# MURI_Compass_V3.net
KiCad netlist of a schematic drawn in EAGLE
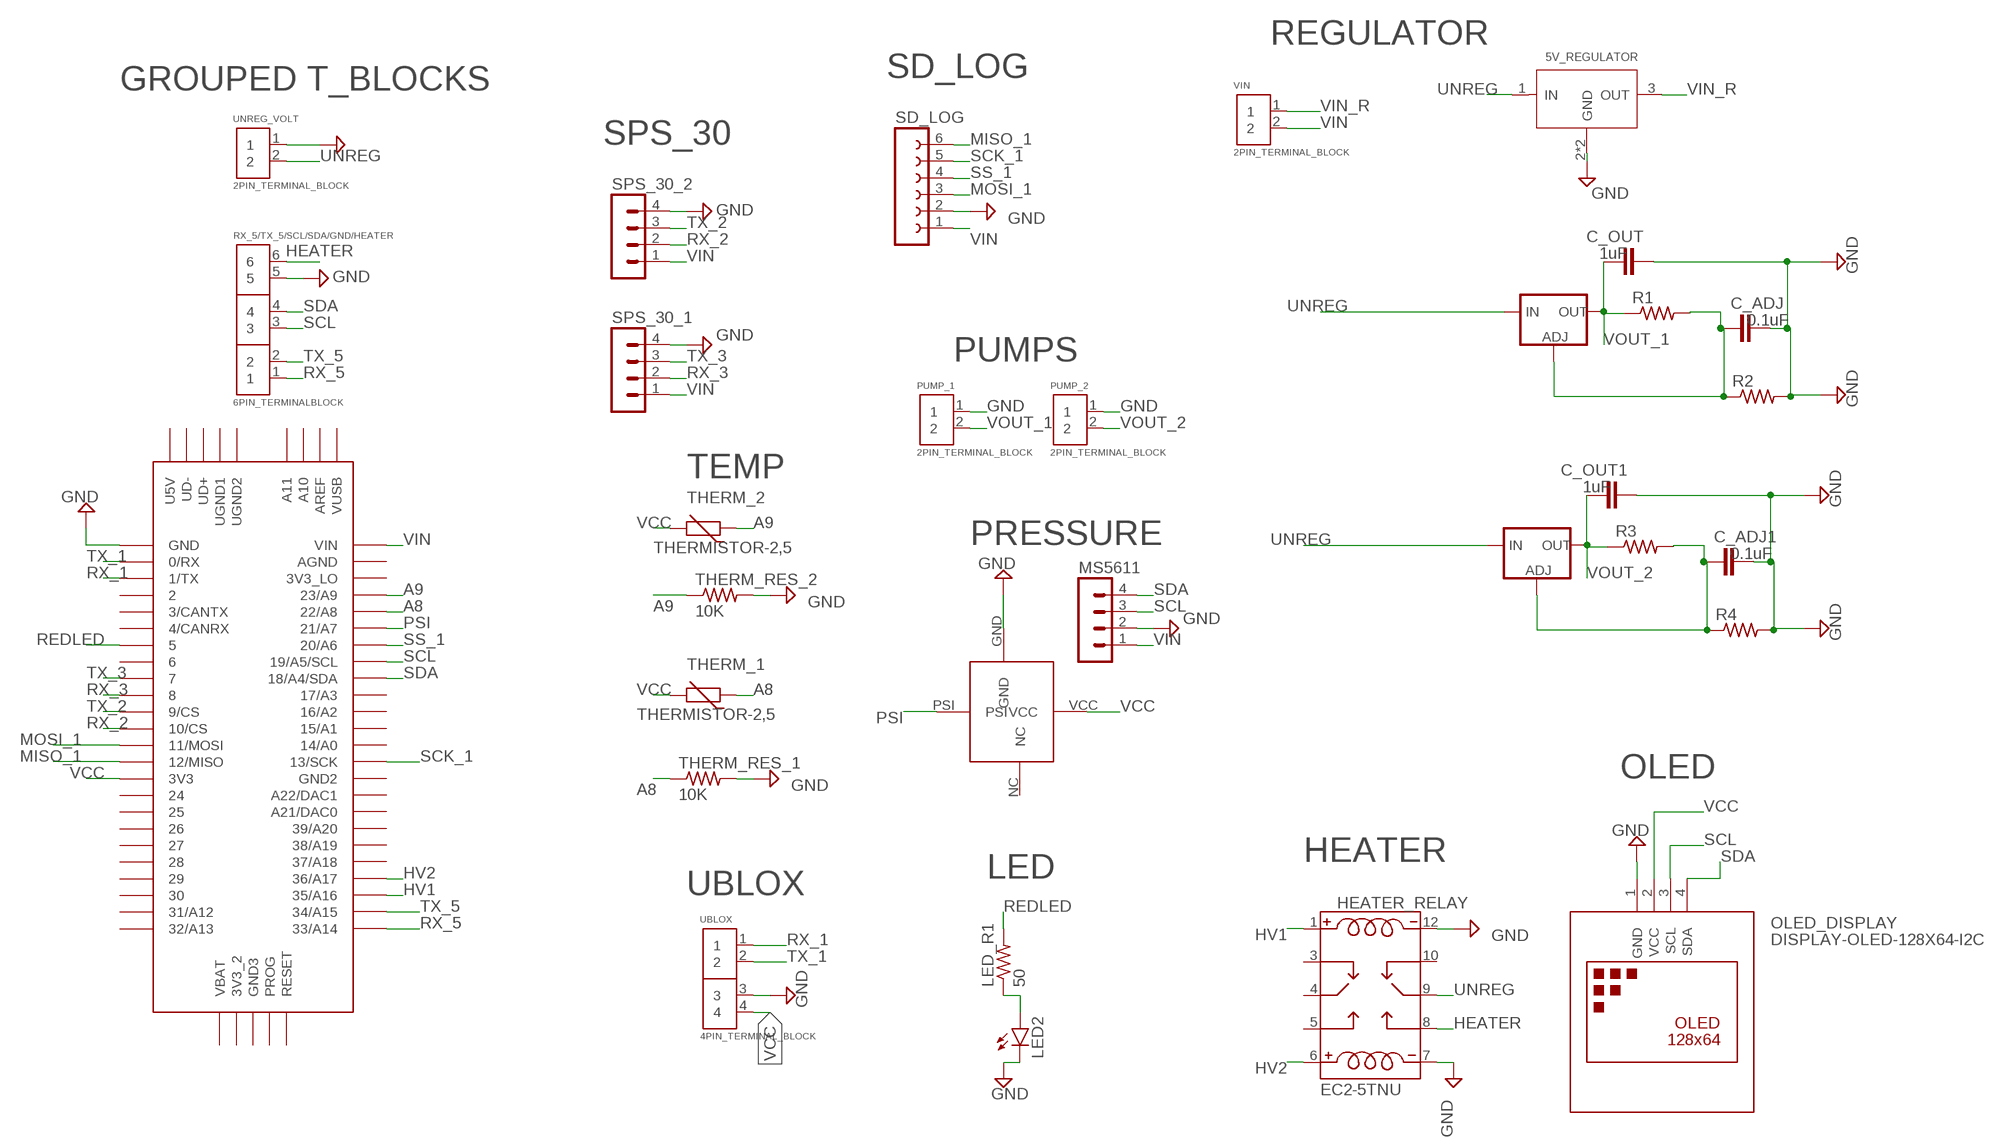
[diagram p0: schematic, sheet 1]

(export (version "E")
  (design (tool "Eeschema 10.0.6"))
  (components
    (comp (ref "5V_REGULATOR")
      (value "PMIC-L7805CV-DG(TO-220)")
      (footprint "eagle-import:TO-220")
      (fields
        (field (name "DIGI-KEY_PART_NUMBER") "497-12404-ND")
        (field (name "MF") "STMicroelectronics")
        (field (name "MP") "L7805CV-DG")
      )
      (libsource (lib "eagle-import") (part "PMIC-L7805CV-DG(TO-220)"))
    )
    (comp (ref "C_ADJ")
      (value "0.1uF")
      (footprint "eagle-import:C2.5-3")
      (libsource (lib "eagle-import") (part "C2,5-3"))
    )
    (comp (ref "C_ADJ1")
      (value "0.1uF")
      (footprint "eagle-import:C2.5-3")
      (libsource (lib "eagle-import") (part "C2,5-3"))
    )
    (comp (ref "C_OUT")
      (value "1uF")
      (footprint "eagle-import:C2.5-3")
      (libsource (lib "eagle-import") (part "C2,5-3"))
    )
    (comp (ref "C_OUT1")
      (value "1uF")
      (footprint "eagle-import:C2.5-3")
      (libsource (lib "eagle-import") (part "C2,5-3"))
    )
    (comp (ref "HEATER_RELAY")
      (value "EC2-5TNU")
      (footprint "eagle-import:RELAY_EC2-5TNU")
      (fields (field (name "MF") "KEMET"))
      (libsource (lib "eagle-import") (part "EC2-5TNU"))
    )
    (comp (ref "LED2")
      (value "TLLR4400")
      (footprint "eagle-import:LED3MM")
      (fields (field (name "MF") "VISHAY SEMICONDUCTOR"))
      (libsource (lib "eagle-import") (part "TLLR4400"))
    )
    (comp (ref "LED_R1")
      (value "50")
      (footprint "eagle-import:0204_7")
      (libsource (lib "eagle-import") (part "resistor_348_R-US_0204/7"))
    )
    (comp (ref "MS5611")
      (value "MA04-1")
      (footprint "eagle-import:MA04-1")
      (libsource (lib "eagle-import") (part "MA04-1"))
    )
    (comp (ref "OLED_DISPLAY")
      (value "DISPLAY-OLED-128X64-I2C")
      (footprint "eagle-import:DISPLAY-OLED-128X64-I2C")
      (libsource (lib "eagle-import") (part "DISPLAY-OLED-128X64-I2C"))
    )
    (comp (ref "PRESSURE_SENSOR")
      (value "SSCSANN015PAAA5")
      (footprint "eagle-import:SSCSANN015PAAA5")
      (libsource (lib "eagle-import") (part "SSCSANN015PAAA5"))
    )
    (comp (ref "PUMP_1")
      (value "2PIN_TERMINAL_BLOCK")
      (footprint "eagle-import:2PIN_TERMINAL_BLOCK")
      (fields
        (field (name "COMMENT") "282834-2")
        (field (name "DIGI-KEY_PART_NUMBER") "A98333-ND")
        (field (name "MF") "TE Connectivity")
      )
      (libsource (lib "eagle-import") (part "2PIN_TERMINAL_BLOCK"))
    )
    (comp (ref "PUMP_2")
      (value "2PIN_TERMINAL_BLOCK")
      (footprint "eagle-import:2PIN_TERMINAL_BLOCK")
      (fields
        (field (name "COMMENT") "282834-2")
        (field (name "DIGI-KEY_PART_NUMBER") "A98333-ND")
        (field (name "MF") "TE Connectivity")
      )
      (libsource (lib "eagle-import") (part "2PIN_TERMINAL_BLOCK"))
    )
    (comp (ref "R1")
      (value "R-US_0204/7")
      (footprint "eagle-import:0204_7")
      (libsource (lib "eagle-import") (part "R-US_0204/7"))
    )
    (comp (ref "R2")
      (value "R-US_0204/7")
      (footprint "eagle-import:0204_7")
      (libsource (lib "eagle-import") (part "R-US_0204/7"))
    )
    (comp (ref "R3")
      (value "R-US_0204/7")
      (footprint "eagle-import:0204_7")
      (libsource (lib "eagle-import") (part "R-US_0204/7"))
    )
    (comp (ref "R4")
      (value "R-US_0204/7")
      (footprint "eagle-import:0204_7")
      (libsource (lib "eagle-import") (part "R-US_0204/7"))
    )
    (comp (ref "RX_5/TX_5/SCL/SDA/GND/HEATER")
      (value "6PIN_TERMINALBLOCK")
      (footprint "eagle-import:6PIN_TERMINALBLOCK")
      (libsource (lib "eagle-import") (part "6PIN_TERMINALBLOCK"))
    )
    (comp (ref "SD_LOG")
      (value "FE06-1")
      (footprint "eagle-import:FE06")
      (libsource (lib "eagle-import") (part "FE06-1"))
    )
    (comp (ref "SPS_30_1")
      (value "MA04-1")
      (footprint "eagle-import:MA04-1")
      (libsource (lib "eagle-import") (part "MA04-1"))
    )
    (comp (ref "SPS_30_2")
      (value "MA04-1")
      (footprint "eagle-import:MA04-1")
      (libsource (lib "eagle-import") (part "MA04-1"))
    )
    (comp (ref "THERM_1")
      (value "THERMISTOR-2,5")
      (footprint "eagle-import:RS-2,5")
      (libsource (lib "eagle-import") (part "THERMISTOR-2,5"))
    )
    (comp (ref "THERM_2")
      (value "THERMISTOR-2,5")
      (footprint "eagle-import:RS-2,5")
      (libsource (lib "eagle-import") (part "THERMISTOR-2,5"))
    )
    (comp (ref "THERM_RES_1")
      (value "10K")
      (footprint "eagle-import:0204_7")
      (libsource (lib "eagle-import") (part "R-US_0204/7"))
    )
    (comp (ref "THERM_RES_2")
      (value "10K")
      (footprint "eagle-import:0204_7")
      (libsource (lib "eagle-import") (part "R-US_0204/7"))
    )
    (comp (ref "U$1")
      (value "TEENSY_3.5/3.6")
      (footprint "eagle-import:TEENSY_3.5_3.6")
      (libsource (lib "eagle-import") (part "TEENSY_3.5/3.6"))
    )
    (comp (ref "U1")
      (value "V_REG_317SINK")
      (footprint "eagle-import:TO220-ADJ")
      (libsource (lib "eagle-import") (part "V_REG_317SINK"))
    )
    (comp (ref "U2")
      (value "V_REG_317SINK")
      (footprint "eagle-import:TO220-ADJ")
      (libsource (lib "eagle-import") (part "V_REG_317SINK"))
    )
    (comp (ref "UBLOX")
      (value "4PIN_TERMINAL_BLOCK")
      (footprint "eagle-import:4PIN_TERMINAL_BLOCK")
      (libsource (lib "eagle-import") (part "4PIN_TERMINAL_BLOCK"))
    )
    (comp (ref "UNREG_VOLT")
      (value "2PIN_TERMINAL_BLOCK")
      (footprint "eagle-import:2PIN_TERMINAL_BLOCK")
      (fields
        (field (name "COMMENT") "282834-2")
        (field (name "DIGI-KEY_PART_NUMBER") "A98333-ND")
        (field (name "MF") "TE Connectivity")
      )
      (libsource (lib "eagle-import") (part "2PIN_TERMINAL_BLOCK"))
    )
    (comp (ref "VIN")
      (value "2PIN_TERMINAL_BLOCK")
      (footprint "eagle-import:2PIN_TERMINAL_BLOCK")
      (fields
        (field (name "COMMENT") "282834-2")
        (field (name "DIGI-KEY_PART_NUMBER") "A98333-ND")
        (field (name "MF") "TE Connectivity")
      )
      (libsource (lib "eagle-import") (part "2PIN_TERMINAL_BLOCK"))
    )
  )
  (nets
    (net (code "1") (name "/A8") (class "Default")
      (node (ref "THERM_1") (pin "1") (pinfunction "1_1") (pintype "passive"))
      (node (ref "THERM_RES_1") (pin "1") (pinfunction "1_1") (pintype "passive"))
      (node (ref "U$1") (pin "22/A8") (pinfunction "22/A8_22/A8") (pintype "bidirectional"))
    )
    (net (code "2") (name "/A9") (class "Default")
      (node (ref "THERM_2") (pin "1") (pinfunction "1_1") (pintype "passive"))
      (node (ref "THERM_RES_2") (pin "1") (pinfunction "1_1") (pintype "passive"))
      (node (ref "U$1") (pin "23/A9") (pinfunction "23/A9_23/A9") (pintype "bidirectional"))
    )
    (net (code "3") (name "/HEATER") (class "Default")
      (node (ref "HEATER_RELAY") (pin "8") (pinfunction "NO_8") (pintype "passive"))
      (node (ref "RX_5/TX_5/SCL/SDA/GND/HEATER") (pin "6") (pinfunction "6_6") (pintype "passive"))
    )
    (net (code "4") (name "/HV1") (class "Default")
      (node (ref "HEATER_RELAY") (pin "1") (pinfunction "C1_1") (pintype "passive"))
      (node (ref "U$1") (pin "35/A16") (pinfunction "35/A16_35/A16") (pintype "bidirectional"))
    )
    (net (code "5") (name "/HV2") (class "Default")
      (node (ref "HEATER_RELAY") (pin "6") (pinfunction "C3_6") (pintype "passive"))
      (node (ref "U$1") (pin "36/A17") (pinfunction "36/A17_36/A17") (pintype "bidirectional"))
    )
    (net (code "6") (name "/MISO_1") (class "Default")
      (node (ref "SD_LOG") (pin "6") (pinfunction "6_6") (pintype "passive"))
      (node (ref "U$1") (pin "12/MISO") (pinfunction "12/MISO_12/MISO") (pintype "bidirectional"))
    )
    (net (code "7") (name "/MOSI_1") (class "Default")
      (node (ref "SD_LOG") (pin "3") (pinfunction "3_3") (pintype "passive"))
      (node (ref "U$1") (pin "11/MOSI") (pinfunction "11/MOSI_11/MOSI") (pintype "bidirectional"))
    )
    (net (code "8") (name "/PSI") (class "Default")
      (node (ref "PRESSURE_SENSOR") (pin "PSI") (pinfunction "PSI_PSI") (pintype "bidirectional"))
      (node (ref "U$1") (pin "21/A7") (pinfunction "21/A7_21/A7") (pintype "bidirectional"))
    )
    (net (code "9") (name "/REDLED") (class "Default")
      (node (ref "LED_R1") (pin "2") (pinfunction "2_2") (pintype "passive"))
      (node (ref "U$1") (pin "5") (pinfunction "5_5") (pintype "bidirectional"))
    )
    (net (code "10") (name "/RX_1") (class "Default")
      (node (ref "U$1") (pin "1/TX") (pinfunction "1/TX_1/TX") (pintype "bidirectional"))
      (node (ref "UBLOX") (pin "1") (pinfunction "1_1") (pintype "passive"))
    )
    (net (code "11") (name "/RX_2") (class "Default")
      (node (ref "SPS_30_2") (pin "2") (pinfunction "2_2") (pintype "passive"))
      (node (ref "U$1") (pin "10/CS") (pinfunction "10/CS_10/CS") (pintype "bidirectional"))
    )
    (net (code "12") (name "/RX_3") (class "Default")
      (node (ref "SPS_30_1") (pin "2") (pinfunction "2_2") (pintype "passive"))
      (node (ref "U$1") (pin "8") (pinfunction "8_8") (pintype "bidirectional"))
    )
    (net (code "13") (name "/RX_5") (class "Default")
      (node (ref "RX_5/TX_5/SCL/SDA/GND/HEATER") (pin "1") (pinfunction "1_1") (pintype "passive"))
      (node (ref "U$1") (pin "33/A14") (pinfunction "33/A14_33/A14") (pintype "bidirectional"))
    )
    (net (code "14") (name "/SCK_1") (class "Default")
      (node (ref "SD_LOG") (pin "5") (pinfunction "5_5") (pintype "passive"))
      (node (ref "U$1") (pin "13/SCK") (pinfunction "13/SCK_13/SCK") (pintype "bidirectional"))
    )
    (net (code "15") (name "/SCL") (class "Default")
      (node (ref "MS5611") (pin "3") (pinfunction "3_3") (pintype "passive"))
      (node (ref "OLED_DISPLAY") (pin "3") (pinfunction "SCL_3") (pintype "bidirectional"))
      (node (ref "RX_5/TX_5/SCL/SDA/GND/HEATER") (pin "3") (pinfunction "3_3") (pintype "passive"))
      (node (ref "U$1") (pin "19/A5/SCL") (pinfunction "19/A5/SCL_19/A5/SCL") (pintype "bidirectional"))
    )
    (net (code "16") (name "/SDA") (class "Default")
      (node (ref "MS5611") (pin "4") (pinfunction "4_4") (pintype "passive"))
      (node (ref "OLED_DISPLAY") (pin "4") (pinfunction "SDA_4") (pintype "bidirectional"))
      (node (ref "RX_5/TX_5/SCL/SDA/GND/HEATER") (pin "4") (pinfunction "4_4") (pintype "passive"))
      (node (ref "U$1") (pin "18/A4/SDA") (pinfunction "18/A4/SDA_18/A4/SDA") (pintype "bidirectional"))
    )
    (net (code "17") (name "/SS_1") (class "Default")
      (node (ref "SD_LOG") (pin "4") (pinfunction "4_4") (pintype "passive"))
      (node (ref "U$1") (pin "20/A6") (pinfunction "20/A6_20/A6") (pintype "bidirectional"))
    )
    (net (code "18") (name "/TX_1") (class "Default")
      (node (ref "U$1") (pin "0/RX") (pinfunction "0/RX_0/RX") (pintype "bidirectional"))
      (node (ref "UBLOX") (pin "2") (pinfunction "2_2") (pintype "passive"))
    )
    (net (code "19") (name "/TX_2") (class "Default")
      (node (ref "SPS_30_2") (pin "3") (pinfunction "3_3") (pintype "passive"))
      (node (ref "U$1") (pin "9/CS") (pinfunction "9/CS_9/CS") (pintype "bidirectional"))
    )
    (net (code "20") (name "/TX_3") (class "Default")
      (node (ref "SPS_30_1") (pin "3") (pinfunction "3_3") (pintype "passive"))
      (node (ref "U$1") (pin "7") (pinfunction "7_7") (pintype "bidirectional"))
    )
    (net (code "21") (name "/TX_5") (class "Default")
      (node (ref "RX_5/TX_5/SCL/SDA/GND/HEATER") (pin "2") (pinfunction "2_2") (pintype "passive"))
      (node (ref "U$1") (pin "34/A15") (pinfunction "34/A15_34/A15") (pintype "bidirectional"))
    )
    (net (code "22") (name "/UNREG") (class "Default")
      (node (ref "5V_REGULATOR") (pin "1") (pinfunction "IN_1") (pintype "bidirectional"))
      (node (ref "HEATER_RELAY") (pin "9") (pinfunction "M_9") (pintype "passive"))
      (node (ref "U1") (pin "IN") (pinfunction "IN_IN") (pintype "input"))
      (node (ref "U2") (pin "IN") (pinfunction "IN_IN") (pintype "input"))
      (node (ref "UNREG_VOLT") (pin "2") (pinfunction "2_2") (pintype "passive"))
    )
    (net (code "23") (name "/VIN") (class "Default")
      (node (ref "MS5611") (pin "1") (pinfunction "1_1") (pintype "passive"))
      (node (ref "SD_LOG") (pin "1") (pinfunction "1_1") (pintype "passive"))
      (node (ref "SPS_30_1") (pin "1") (pinfunction "1_1") (pintype "passive"))
      (node (ref "SPS_30_2") (pin "1") (pinfunction "1_1") (pintype "passive"))
      (node (ref "U$1") (pin "VIN") (pinfunction "VIN_VIN") (pintype "bidirectional"))
      (node (ref "VIN") (pin "2") (pinfunction "2_2") (pintype "passive"))
    )
    (net (code "24") (name "/VIN_R") (class "Default")
      (node (ref "5V_REGULATOR") (pin "3") (pinfunction "OUT_3") (pintype "bidirectional"))
      (node (ref "VIN") (pin "1") (pinfunction "1_1") (pintype "passive"))
    )
    (net (code "25") (name "/VOUT_1") (class "Default")
      (node (ref "C_OUT") (pin "1") (pinfunction "1_1") (pintype "passive"))
      (node (ref "PUMP_1") (pin "2") (pinfunction "2_2") (pintype "passive"))
      (node (ref "R1") (pin "1") (pinfunction "1_1") (pintype "passive"))
      (node (ref "U1") (pin "OUT") (pinfunction "OUT_OUT") (pintype "output"))
    )
    (net (code "26") (name "/VOUT_2") (class "Default")
      (node (ref "C_OUT1") (pin "1") (pinfunction "1_1") (pintype "passive"))
      (node (ref "PUMP_2") (pin "2") (pinfunction "2_2") (pintype "passive"))
      (node (ref "R3") (pin "1") (pinfunction "1_1") (pintype "passive"))
      (node (ref "U2") (pin "OUT") (pinfunction "OUT_OUT") (pintype "output"))
    )
    (net (code "27") (name "GND") (class "Default")
      (node (ref "5V_REGULATOR") (pin "2") (pinfunction "GND_2") (pintype "bidirectional"))
      (node (ref "5V_REGULATOR") (pin "HEAT") (pinfunction "GND_HEAT") (pintype "bidirectional"))
      (node (ref "C_ADJ") (pin "1") (pinfunction "1_1") (pintype "passive"))
      (node (ref "C_ADJ1") (pin "1") (pinfunction "1_1") (pintype "passive"))
      (node (ref "C_OUT") (pin "2") (pinfunction "2_2") (pintype "passive"))
      (node (ref "C_OUT1") (pin "2") (pinfunction "2_2") (pintype "passive"))
      (node (ref "HEATER_RELAY") (pin "12") (pinfunction "C2_12") (pintype "passive"))
      (node (ref "HEATER_RELAY") (pin "7") (pinfunction "C4_7") (pintype "passive"))
      (node (ref "LED2") (pin "K") (pinfunction "C_K") (pintype "passive"))
      (node (ref "MS5611") (pin "2") (pinfunction "2_2") (pintype "passive"))
      (node (ref "OLED_DISPLAY") (pin "1") (pinfunction "GND_1") (pintype "power_in"))
      (node (ref "PRESSURE_SENSOR") (pin "GND") (pinfunction "GND_GND") (pintype "bidirectional"))
      (node (ref "PUMP_1") (pin "1") (pinfunction "1_1") (pintype "passive"))
      (node (ref "PUMP_2") (pin "1") (pinfunction "1_1") (pintype "passive"))
      (node (ref "R2") (pin "2") (pinfunction "2_2") (pintype "passive"))
      (node (ref "R4") (pin "2") (pinfunction "2_2") (pintype "passive"))
      (node (ref "RX_5/TX_5/SCL/SDA/GND/HEATER") (pin "5") (pinfunction "5_5") (pintype "passive"))
      (node (ref "SD_LOG") (pin "2") (pinfunction "2_2") (pintype "passive"))
      (node (ref "SPS_30_1") (pin "4") (pinfunction "4_4") (pintype "passive"))
      (node (ref "SPS_30_2") (pin "4") (pinfunction "4_4") (pintype "passive"))
      (node (ref "THERM_RES_1") (pin "2") (pinfunction "2_2") (pintype "passive"))
      (node (ref "THERM_RES_2") (pin "2") (pinfunction "2_2") (pintype "passive"))
      (node (ref "U$1") (pin "GND") (pinfunction "GND_GND") (pintype "bidirectional"))
      (node (ref "UBLOX") (pin "3") (pinfunction "3_3") (pintype "passive"))
      (node (ref "UNREG_VOLT") (pin "1") (pinfunction "1_1") (pintype "passive"))
    )
    (net (code "28") (name "Net-(C_ADJ-Pad2)") (class "Default")
      (node (ref "C_ADJ") (pin "2") (pinfunction "2_2") (pintype "passive"))
      (node (ref "R1") (pin "2") (pinfunction "2_2") (pintype "passive"))
      (node (ref "R2") (pin "1") (pinfunction "1_1") (pintype "passive"))
      (node (ref "U1") (pin "ADJ") (pinfunction "ADJ_ADJ") (pintype "input"))
    )
    (net (code "29") (name "Net-(C_ADJ1-Pad2)") (class "Default")
      (node (ref "C_ADJ1") (pin "2") (pinfunction "2_2") (pintype "passive"))
      (node (ref "R3") (pin "2") (pinfunction "2_2") (pintype "passive"))
      (node (ref "R4") (pin "1") (pinfunction "1_1") (pintype "passive"))
      (node (ref "U2") (pin "ADJ") (pinfunction "ADJ_ADJ") (pintype "input"))
    )
    (net (code "30") (name "Net-(LED2-PadA)") (class "Default")
      (node (ref "LED2") (pin "A") (pinfunction "A_A") (pintype "passive"))
      (node (ref "LED_R1") (pin "1") (pinfunction "1_1") (pintype "passive"))
    )
    (net (code "31") (name "VCC") (class "Default")
      (node (ref "OLED_DISPLAY") (pin "2") (pinfunction "VCC_2") (pintype "power_in"))
      (node (ref "PRESSURE_SENSOR") (pin "VCC") (pinfunction "VCC_VCC") (pintype "bidirectional"))
      (node (ref "THERM_1") (pin "2") (pinfunction "2_2") (pintype "passive"))
      (node (ref "THERM_2") (pin "2") (pinfunction "2_2") (pintype "passive"))
      (node (ref "U$1") (pin "3V3") (pinfunction "3V3_3V3") (pintype "bidirectional"))
      (node (ref "UBLOX") (pin "4") (pinfunction "4_4") (pintype "passive"))
    )
    (net (code "32") (name "unconnected-(HEATER_RELAY-M1-Pad4)") (class "Default")
      (node (ref "HEATER_RELAY") (pin "4") (pinfunction "M1_4") (pintype "passive"))
    )
    (net (code "33") (name "unconnected-(HEATER_RELAY-NC-Pad10)") (class "Default")
      (node (ref "HEATER_RELAY") (pin "10") (pinfunction "NC_10") (pintype "passive"))
    )
    (net (code "34") (name "unconnected-(HEATER_RELAY-NC1-Pad3)") (class "Default")
      (node (ref "HEATER_RELAY") (pin "3") (pinfunction "NC1_3") (pintype "passive"))
    )
    (net (code "35") (name "unconnected-(HEATER_RELAY-NO1-Pad5)") (class "Default")
      (node (ref "HEATER_RELAY") (pin "5") (pinfunction "NO1_5") (pintype "passive"))
    )
    (net (code "36") (name "unconnected-(PRESSURE_SENSOR-PadNC)") (class "Default")
      (node (ref "PRESSURE_SENSOR") (pin "NC") (pinfunction "NC_NC") (pintype "bidirectional"))
    )
    (net (code "37") (name "unconnected-(U$1-A21{slash}DAC0-Pad21{slash}DAC0)") (class "Default")
      (node (ref "U$1") (pin "21/DAC0") (pinfunction "A21/DAC0_21/DAC0") (pintype "bidirectional"))
    )
    (net (code "38") (name "unconnected-(U$1-Pad2)") (class "Default")
      (node (ref "U$1") (pin "2") (pinfunction "2_2") (pintype "bidirectional"))
    )
    (net (code "39") (name "unconnected-(U$1-Pad3V3_2)") (class "Default")
      (node (ref "U$1") (pin "3V3_2") (pinfunction "3V3_2_3V3_2") (pintype "bidirectional"))
    )
    (net (code "40") (name "unconnected-(U$1-Pad3V3_LO)") (class "Default")
      (node (ref "U$1") (pin "3V3_LO") (pinfunction "3V3_LO_3V3_LO") (pintype "bidirectional"))
    )
    (net (code "41") (name "unconnected-(U$1-Pad3{slash}CANTX)") (class "Default")
      (node (ref "U$1") (pin "3/CANTX") (pinfunction "3/CANTX_3/CANTX") (pintype "bidirectional"))
    )
    (net (code "42") (name "unconnected-(U$1-Pad4{slash}CANRX)") (class "Default")
      (node (ref "U$1") (pin "4/CANRX") (pinfunction "4/CANRX_4/CANRX") (pintype "bidirectional"))
    )
    (net (code "43") (name "unconnected-(U$1-Pad6)") (class "Default")
      (node (ref "U$1") (pin "6") (pinfunction "6_6") (pintype "bidirectional"))
    )
    (net (code "44") (name "unconnected-(U$1-Pad14{slash}A0)") (class "Default")
      (node (ref "U$1") (pin "14/A0") (pinfunction "14/A0_14/A0") (pintype "bidirectional"))
    )
    (net (code "45") (name "unconnected-(U$1-Pad15{slash}A1)") (class "Default")
      (node (ref "U$1") (pin "15/A1") (pinfunction "15/A1_15/A1") (pintype "bidirectional"))
    )
    (net (code "46") (name "unconnected-(U$1-Pad16{slash}A2)") (class "Default")
      (node (ref "U$1") (pin "16/A2") (pinfunction "16/A2_16/A2") (pintype "bidirectional"))
    )
    (net (code "47") (name "unconnected-(U$1-Pad17{slash}A3)") (class "Default")
      (node (ref "U$1") (pin "17/A3") (pinfunction "17/A3_17/A3") (pintype "bidirectional"))
    )
    (net (code "48") (name "unconnected-(U$1-Pad24)") (class "Default")
      (node (ref "U$1") (pin "24") (pinfunction "24_24") (pintype "bidirectional"))
    )
    (net (code "49") (name "unconnected-(U$1-Pad25)") (class "Default")
      (node (ref "U$1") (pin "25") (pinfunction "25_25") (pintype "bidirectional"))
    )
    (net (code "50") (name "unconnected-(U$1-Pad26)") (class "Default")
      (node (ref "U$1") (pin "26") (pinfunction "26_26") (pintype "bidirectional"))
    )
    (net (code "51") (name "unconnected-(U$1-Pad27)") (class "Default")
      (node (ref "U$1") (pin "27") (pinfunction "27_27") (pintype "bidirectional"))
    )
    (net (code "52") (name "unconnected-(U$1-Pad28)") (class "Default")
      (node (ref "U$1") (pin "28") (pinfunction "28_28") (pintype "bidirectional"))
    )
    (net (code "53") (name "unconnected-(U$1-Pad29)") (class "Default")
      (node (ref "U$1") (pin "29") (pinfunction "29_29") (pintype "bidirectional"))
    )
    (net (code "54") (name "unconnected-(U$1-Pad30)") (class "Default")
      (node (ref "U$1") (pin "30") (pinfunction "30_30") (pintype "bidirectional"))
    )
    (net (code "55") (name "unconnected-(U$1-Pad31{slash}A12)") (class "Default")
      (node (ref "U$1") (pin "31/A12") (pinfunction "31/A12_31/A12") (pintype "bidirectional"))
    )
    (net (code "56") (name "unconnected-(U$1-Pad32{slash}A13)") (class "Default")
      (node (ref "U$1") (pin "32/A13") (pinfunction "32/A13_32/A13") (pintype "bidirectional"))
    )
    (net (code "57") (name "unconnected-(U$1-Pad37{slash}A18)") (class "Default")
      (node (ref "U$1") (pin "37/A18") (pinfunction "37/A18_37/A18") (pintype "bidirectional"))
    )
    (net (code "58") (name "unconnected-(U$1-Pad38{slash}A19)") (class "Default")
      (node (ref "U$1") (pin "38/A19") (pinfunction "38/A19_38/A19") (pintype "bidirectional"))
    )
    (net (code "59") (name "unconnected-(U$1-Pad39{slash}A20)") (class "Default")
      (node (ref "U$1") (pin "39/A20") (pinfunction "39/A20_39/A20") (pintype "bidirectional"))
    )
    (net (code "60") (name "unconnected-(U$1-PadA10)") (class "Default")
      (node (ref "U$1") (pin "A10") (pinfunction "A10_A10") (pintype "bidirectional"))
    )
    (net (code "61") (name "unconnected-(U$1-PadA11)") (class "Default")
      (node (ref "U$1") (pin "A11") (pinfunction "A11_A11") (pintype "bidirectional"))
    )
    (net (code "62") (name "unconnected-(U$1-PadA22{slash}DAC1)") (class "Default")
      (node (ref "U$1") (pin "A22/DAC1") (pinfunction "A22/DAC1_A22/DAC1") (pintype "bidirectional"))
    )
    (net (code "63") (name "unconnected-(U$1-PadAGND)") (class "Default")
      (node (ref "U$1") (pin "AGND") (pinfunction "AGND_AGND") (pintype "bidirectional"))
    )
    (net (code "64") (name "unconnected-(U$1-PadAREF)") (class "Default")
      (node (ref "U$1") (pin "AREF") (pinfunction "AREF_AREF") (pintype "bidirectional"))
    )
    (net (code "65") (name "unconnected-(U$1-PadGND2)") (class "Default")
      (node (ref "U$1") (pin "GND2") (pinfunction "GND2_GND2") (pintype "bidirectional"))
    )
    (net (code "66") (name "unconnected-(U$1-PadGND3)") (class "Default")
      (node (ref "U$1") (pin "GND3") (pinfunction "GND3_GND3") (pintype "bidirectional"))
    )
    (net (code "67") (name "unconnected-(U$1-PadPROG)") (class "Default")
      (node (ref "U$1") (pin "PROG") (pinfunction "PROG_PROG") (pintype "bidirectional"))
    )
    (net (code "68") (name "unconnected-(U$1-PadRESET)") (class "Default")
      (node (ref "U$1") (pin "RESET") (pinfunction "RESET_RESET") (pintype "bidirectional"))
    )
    (net (code "69") (name "unconnected-(U$1-PadU5V)") (class "Default")
      (node (ref "U$1") (pin "U5V") (pinfunction "U5V_U5V") (pintype "bidirectional"))
    )
    (net (code "70") (name "unconnected-(U$1-PadUD+)") (class "Default")
      (node (ref "U$1") (pin "UD+") (pinfunction "UD+_UD+") (pintype "bidirectional"))
    )
    (net (code "71") (name "unconnected-(U$1-PadUD-)") (class "Default")
      (node (ref "U$1") (pin "UD-") (pinfunction "UD-_UD-") (pintype "bidirectional"))
    )
    (net (code "72") (name "unconnected-(U$1-PadUGND1)") (class "Default")
      (node (ref "U$1") (pin "UGND1") (pinfunction "UGND1_UGND1") (pintype "bidirectional"))
    )
    (net (code "73") (name "unconnected-(U$1-PadUGND2)") (class "Default")
      (node (ref "U$1") (pin "UGND2") (pinfunction "UGND2_UGND2") (pintype "bidirectional"))
    )
    (net (code "74") (name "unconnected-(U$1-PadVBAT)") (class "Default")
      (node (ref "U$1") (pin "VBAT") (pinfunction "VBAT_VBAT") (pintype "bidirectional"))
    )
    (net (code "75") (name "unconnected-(U$1-PadVUSB)") (class "Default")
      (node (ref "U$1") (pin "VUSB") (pinfunction "VUSB_VUSB") (pintype "bidirectional"))
    )
  )
)
